# MicroController.net
KiCad netlist of a schematic drawn in Altium Designer
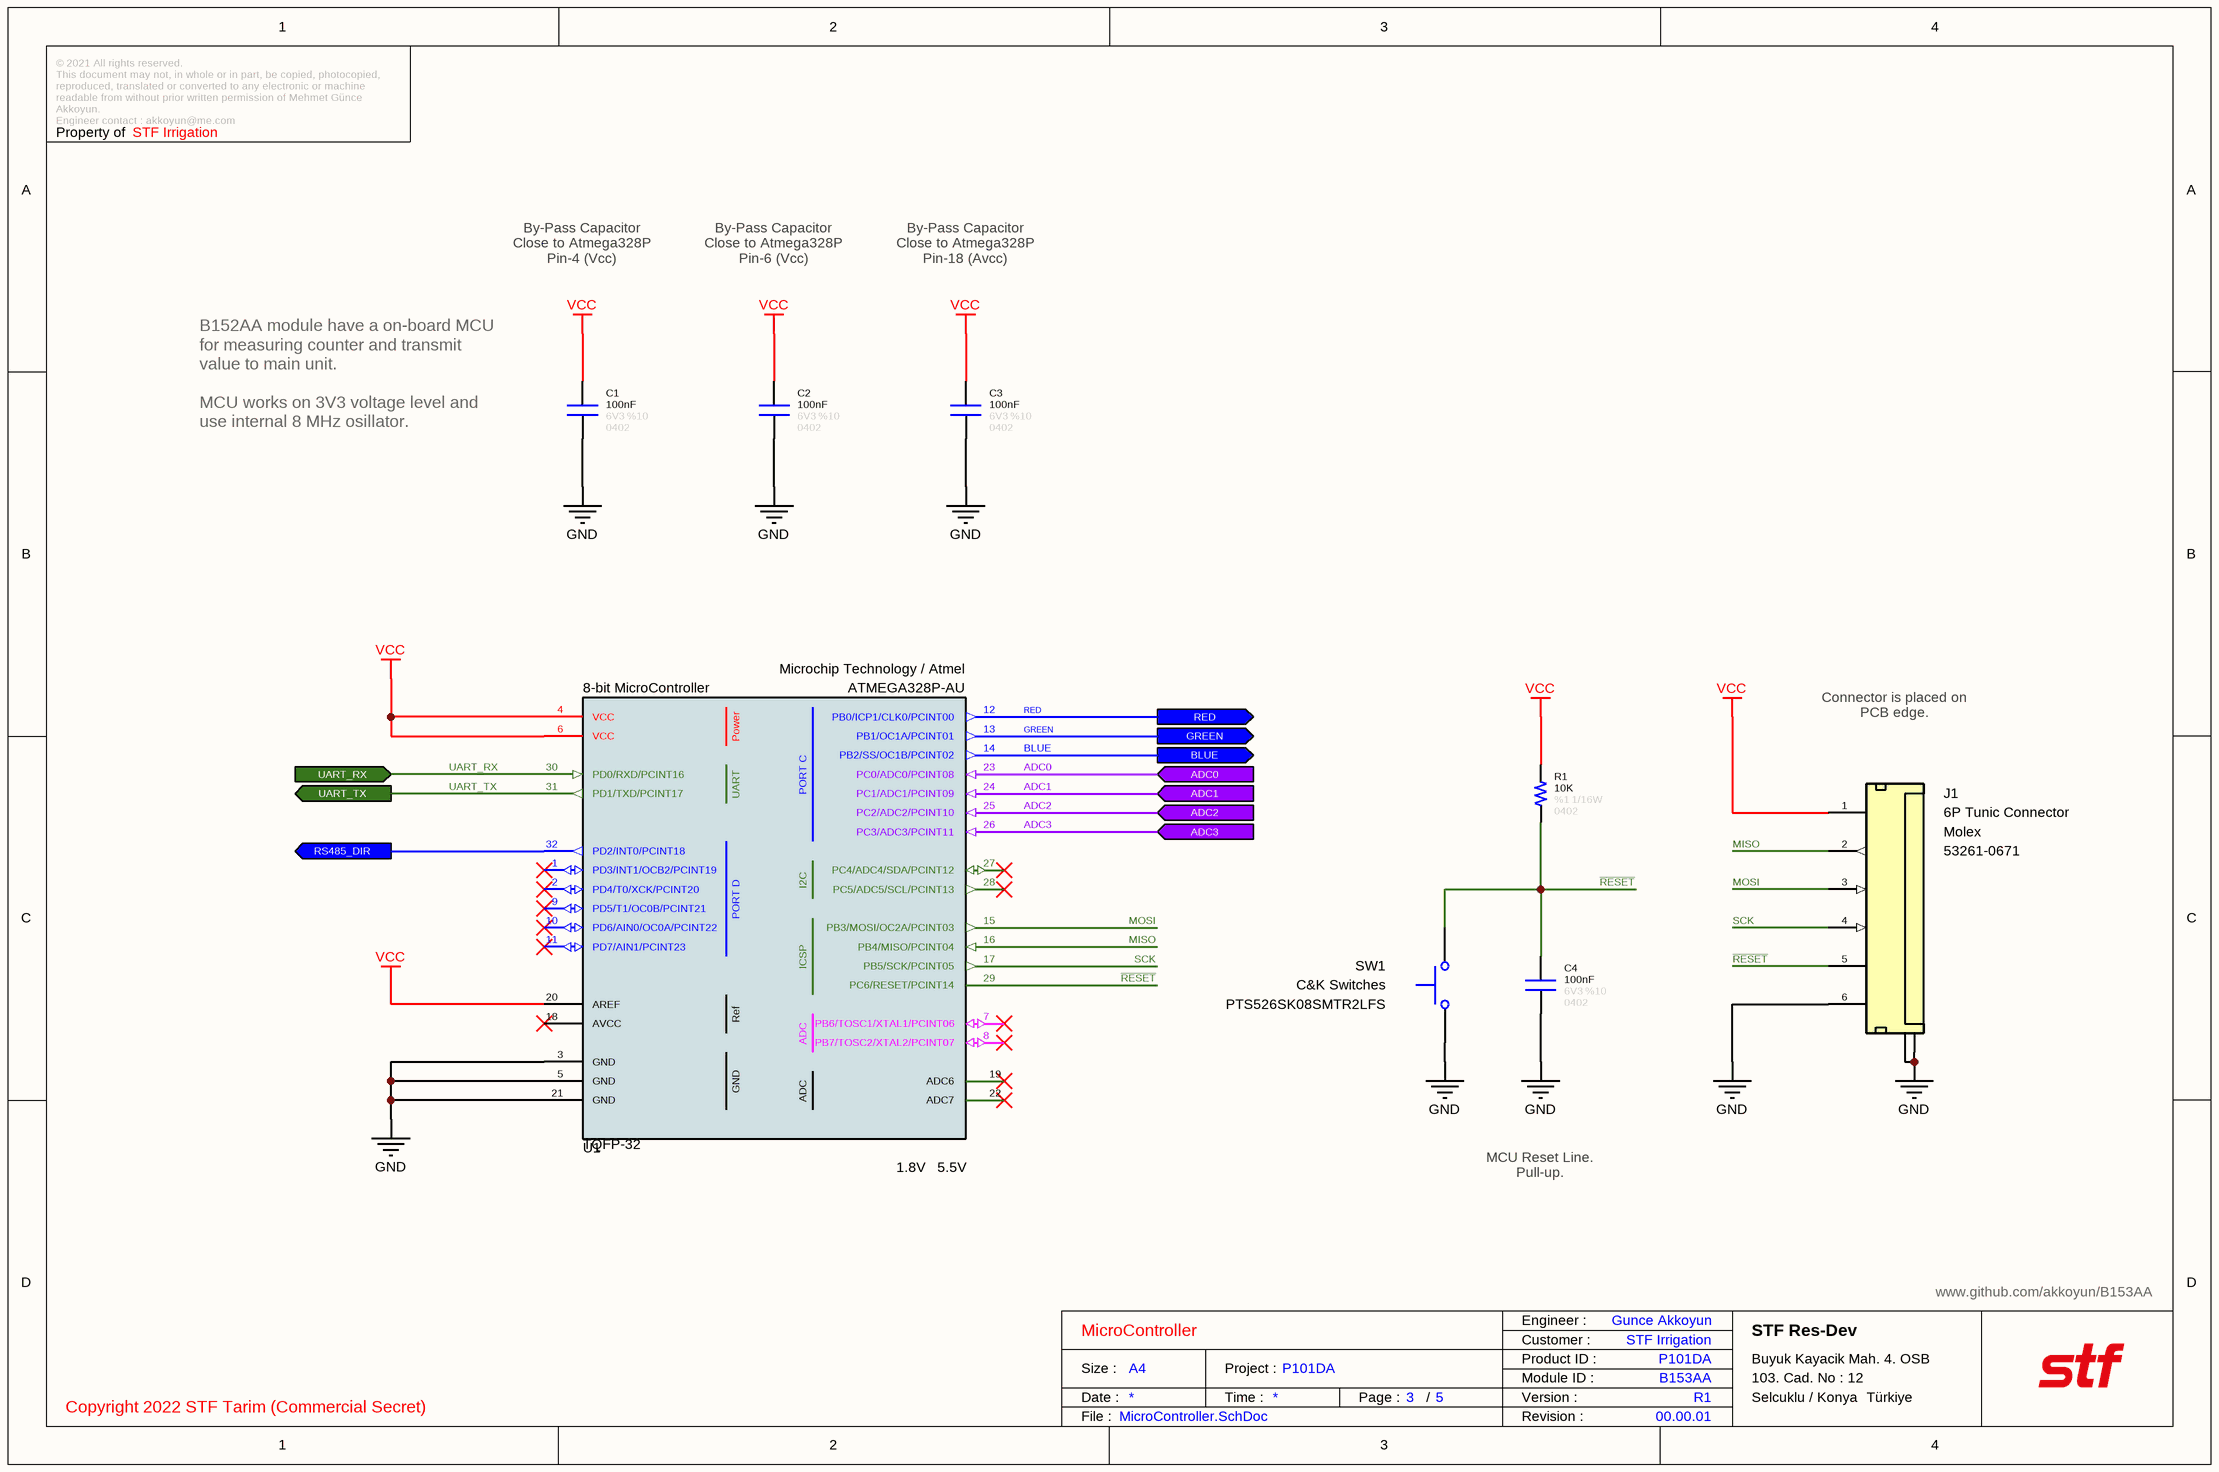
[diagram p0: MicroController.SchDoc]

(export (version "E")
  (design (tool "Eeschema 10.0.6"))
  (components
    (comp (ref "C1")
      (value "100nF")
      (footprint "CAPACITOR_0402")
      (description "Capacitor - 100nF [0402-6V3] (Ceramic)")
      (fields
        (field (name "MANUFACTURER PART NUMBER") "04026D104KAT4A")
        (field (name "TOLERANCE") "%10")
        (field (name "VOLTAGE") "6V3")
        (field (name "CASE") "0402")
        (field (name "Comment") "Capacitor - 100nF [0402] (Ceramic)")
      )
      (libsource (lib "P101DA_Library") (part "Capacitor - 100nF [0402-6V3]"))
    )
    (comp (ref "C2")
      (value "100nF")
      (footprint "CAPACITOR_0402")
      (description "Capacitor - 100nF [0402-6V3] (Ceramic)")
      (fields
        (field (name "MANUFACTURER PART NUMBER") "04026D104KAT4A")
        (field (name "TOLERANCE") "%10")
        (field (name "VOLTAGE") "6V3")
        (field (name "CASE") "0402")
        (field (name "Comment") "Capacitor - 100nF [0402] (Ceramic)")
      )
      (libsource (lib "P101DA_Library") (part "Capacitor - 100nF [0402-6V3]"))
    )
    (comp (ref "C3")
      (value "100nF")
      (footprint "CAPACITOR_0402")
      (description "Capacitor - 100nF [0402-6V3] (Ceramic)")
      (fields
        (field (name "MANUFACTURER PART NUMBER") "04026D104KAT4A")
        (field (name "TOLERANCE") "%10")
        (field (name "VOLTAGE") "6V3")
        (field (name "CASE") "0402")
        (field (name "Comment") "Capacitor - 100nF [0402] (Ceramic)")
      )
      (libsource (lib "P101DA_Library") (part "Capacitor - 100nF [0402-6V3]"))
    )
    (comp (ref "C4")
      (value "100nF")
      (footprint "CAPACITOR_0402")
      (description "Capacitor - 100nF [0402-6V3] (Ceramic)")
      (fields
        (field (name "MANUFACTURER PART NUMBER") "04026D104KAT4A")
        (field (name "TOLERANCE") "%10")
        (field (name "VOLTAGE") "6V3")
        (field (name "CASE") "0402")
        (field (name "Comment") "Capacitor - 100nF [0402] (Ceramic)")
      )
      (libsource (lib "P101DA_Library") (part "Capacitor - 100nF [0402-6V3]"))
    )
    (comp (ref "J1")
      (value "6P Tunic Connector")
      (footprint "Connector_Tunic 6P")
      (description "Mini Tunic Connector with 6P")
      (fields
        (field (name "MANUFACTURER PART NUMBER") "53261-0671")
        (field (name "MANUFACTURER NAME") "Molex")
      )
      (libsource (lib "P101DA_Library") (part "Connector - Mini Tunic 6P (1.25)"))
    )
    (comp (ref "R1")
      (value "10K")
      (footprint "RESISTOR_0402")
      (description "Thick Film Resistors - SMD 1/16 W 10 KOhm 1%")
      (fields
        (field (name "MANUFACTURER PART NUMBER") "CRCW040210K0FKED")
        (field (name "TOLERANCE") "%1")
        (field (name "CASE") "0402")
        (field (name "POWER") "1/16W")
        (field (name "Comment") "10K - 0402 - %1 - 1/16W")
      )
      (libsource (lib "P101DA_Library") (part "Resistor - 10K [0402]"))
    )
    (comp (ref "SW1")
      (value "PTS526SK08SMTR2LFS")
      (footprint "PTS526_Switch")
      (description "Switch Tactile N.O. SPST Flush Round Button Gull Wing 0.05A 12VDC 200000Cycles 2.45N SMD T/R")
      (fields
        (field (name "MANUFACTURER NAME") "C&K Switches")
        (field (name "MANUFACTURER PART NUMBER") "PTS526SK08SMTR2LFS")
      )
      (libsource (lib "P101DA_Library") (part "Switch - Push Button"))
    )
    (comp (ref "U1")
      (value "8-bit MicroController")
      (footprint "TQFN-32")
      (description "8-bit Microcontrollers - MCU 32KB In-system Flash 20MHz 1.8V-5.5V")
      (fields
        (field (name "SUPPLY VOLTAGE - MAX") "5.5V")
        (field (name "SUPPLY VOLTAGE - MIN") "1.8V")
        (field (name "MANUFACTURER NAME") "Microchip Technology / Atmel")
        (field (name "MANUFACTURER PART NUMBER") "ATMEGA328P-AU")
        (field (name "CASE") "TQFP-32")
      )
      (libsource (lib "P101DA_Library") (part "IC - ATMEGA328P-AU"))
    )
  )
  (nets
    (net (code "1") (name "/ADC0") (class "Default")
      (node (ref "U1") (pin "23") (pinfunction "PC0/ADC0/PCINT08_23") (pintype "input"))
    )
    (net (code "2") (name "/ADC1") (class "Default")
      (node (ref "U1") (pin "24") (pinfunction "PC1/ADC1/PCINT09_24") (pintype "input"))
    )
    (net (code "3") (name "/ADC2") (class "Default")
      (node (ref "U1") (pin "25") (pinfunction "PC2/ADC2/PCINT10_25") (pintype "input"))
    )
    (net (code "4") (name "/ADC3") (class "Default")
      (node (ref "U1") (pin "26") (pinfunction "PC3/ADC3/PCINT11_26") (pintype "input"))
    )
    (net (code "5") (name "/BLUE") (class "Default")
      (node (ref "U1") (pin "14") (pinfunction "PB2/SS/OC1B/PCINT02_14") (pintype "output"))
    )
    (net (code "6") (name "/GREEN") (class "Default")
      (node (ref "U1") (pin "13") (pinfunction "PB1/OC1A/PCINT01_13") (pintype "output"))
    )
    (net (code "7") (name "/MISO") (class "Default")
      (node (ref "J1") (pin "2") (pinfunction "M_DRV_2") (pintype "output"))
      (node (ref "U1") (pin "16") (pinfunction "PB4/MISO/PCINT04_16") (pintype "input"))
    )
    (net (code "8") (name "/MOSI") (class "Default")
      (node (ref "J1") (pin "3") (pinfunction "M_DRV_3") (pintype "input"))
      (node (ref "U1") (pin "15") (pinfunction "PB3/MOSI/OC2A/PCINT03_15") (pintype "output"))
    )
    (net (code "9") (name "/RED") (class "Default")
      (node (ref "U1") (pin "12") (pinfunction "PB0/ICP1/CLK0/PCINT00_12") (pintype "output"))
    )
    (net (code "10") (name "/RS485_DIR") (class "Default")
      (node (ref "U1") (pin "32") (pinfunction "PD2/INT0/PCINT18_32") (pintype "output"))
    )
    (net (code "11") (name "/SCK") (class "Default")
      (node (ref "J1") (pin "4") (pinfunction "M_DRV_4") (pintype "input"))
      (node (ref "U1") (pin "17") (pinfunction "PB5/SCK/PCINT05_17") (pintype "output"))
    )
    (net (code "12") (name "/UART_RX") (class "Default")
      (node (ref "U1") (pin "30") (pinfunction "PD0/RXD/PCINT16_30") (pintype "input"))
    )
    (net (code "13") (name "/UART_TX") (class "Default")
      (node (ref "U1") (pin "31") (pinfunction "PD1/TXD/PCINT17_31") (pintype "output"))
    )
    (net (code "14") (name "/~{RESET}") (class "Default")
      (node (ref "C4") (pin "2") (pinfunction "2_2") (pintype "passive"))
      (node (ref "J1") (pin "5") (pinfunction "M_DRV_5") (pintype "passive"))
      (node (ref "R1") (pin "1") (pinfunction "1_1") (pintype "passive"))
      (node (ref "SW1") (pin "2") (pinfunction "COM_2") (pintype "passive"))
      (node (ref "U1") (pin "29") (pinfunction "PC6/RESET/PCINT14_29") (pintype "passive"))
    )
    (net (code "15") (name "GND") (class "Default")
      (node (ref "C1") (pin "1") (pinfunction "1_1") (pintype "passive"))
      (node (ref "C2") (pin "1") (pinfunction "1_1") (pintype "passive"))
      (node (ref "C3") (pin "1") (pinfunction "1_1") (pintype "passive"))
      (node (ref "C4") (pin "1") (pinfunction "1_1") (pintype "passive"))
      (node (ref "J1") (pin "6") (pinfunction "M_DRV_6") (pintype "passive"))
      (node (ref "J1") (pin "7") (pinfunction "GND_7") (pintype "passive"))
      (node (ref "J1") (pin "8") (pinfunction "GND_8") (pintype "passive"))
      (node (ref "SW1") (pin "1") (pinfunction "NC_1") (pintype "passive"))
      (node (ref "U1") (pin "21") (pinfunction "GND_21") (pintype "power_in"))
      (node (ref "U1") (pin "3") (pinfunction "GND_3") (pintype "power_in"))
      (node (ref "U1") (pin "5") (pinfunction "GND_5") (pintype "power_in"))
    )
    (net (code "16") (name "VCC") (class "Default")
      (node (ref "C1") (pin "2") (pinfunction "2_2") (pintype "passive"))
      (node (ref "C2") (pin "2") (pinfunction "2_2") (pintype "passive"))
      (node (ref "C3") (pin "2") (pinfunction "2_2") (pintype "passive"))
      (node (ref "J1") (pin "1") (pinfunction "VBAT_1") (pintype "passive"))
      (node (ref "R1") (pin "2") (pinfunction "2_2") (pintype "passive"))
      (node (ref "U1") (pin "20") (pinfunction "AREF_20") (pintype "passive"))
      (node (ref "U1") (pin "4") (pinfunction "VCC_4") (pintype "power_in"))
      (node (ref "U1") (pin "6") (pinfunction "VCC_6") (pintype "power_in"))
    )
    (net (code "17") (name "unconnected-(U1-ADC6-Pad19)") (class "Default")
      (node (ref "U1") (pin "19") (pinfunction "ADC6_19") (pintype "passive+no_connect"))
    )
    (net (code "18") (name "unconnected-(U1-ADC7-Pad22)") (class "Default")
      (node (ref "U1") (pin "22") (pinfunction "ADC7_22") (pintype "passive+no_connect"))
    )
    (net (code "19") (name "unconnected-(U1-AVCC-Pad18)") (class "Default")
      (node (ref "U1") (pin "18") (pinfunction "AVCC_18") (pintype "passive+no_connect"))
    )
    (net (code "20") (name "unconnected-(U1-PB6{slash}TOSC1{slash}XTAL1{slash}PCINT06-Pad7)") (class "Default")
      (node (ref "U1") (pin "7") (pinfunction "PB6/TOSC1/XTAL1/PCINT06_7") (pintype "bidirectional+no_connect"))
    )
    (net (code "21") (name "unconnected-(U1-PB7{slash}TOSC2{slash}XTAL2{slash}PCINT07-Pad8)") (class "Default")
      (node (ref "U1") (pin "8") (pinfunction "PB7/TOSC2/XTAL2/PCINT07_8") (pintype "bidirectional+no_connect"))
    )
    (net (code "22") (name "unconnected-(U1-PC4{slash}ADC4{slash}SDA{slash}PCINT12-Pad27)") (class "Default")
      (node (ref "U1") (pin "27") (pinfunction "PC4/ADC4/SDA/PCINT12_27") (pintype "bidirectional+no_connect"))
    )
    (net (code "23") (name "unconnected-(U1-PC5{slash}ADC5{slash}SCL{slash}PCINT13-Pad28)") (class "Default")
      (node (ref "U1") (pin "28") (pinfunction "PC5/ADC5/SCL/PCINT13_28") (pintype "output+no_connect"))
    )
    (net (code "24") (name "unconnected-(U1-PD3{slash}INT1{slash}OCB2{slash}PCINT19-Pad1)") (class "Default")
      (node (ref "U1") (pin "1") (pinfunction "PD3/INT1/OCB2/PCINT19_1") (pintype "bidirectional+no_connect"))
    )
    (net (code "25") (name "unconnected-(U1-PD4{slash}T0{slash}XCK{slash}PCINT20-Pad2)") (class "Default")
      (node (ref "U1") (pin "2") (pinfunction "PD4/T0/XCK/PCINT20_2") (pintype "bidirectional+no_connect"))
    )
    (net (code "26") (name "unconnected-(U1-PD5{slash}T1{slash}OC0B{slash}PCINT21-Pad9)") (class "Default")
      (node (ref "U1") (pin "9") (pinfunction "PD5/T1/OC0B/PCINT21_9") (pintype "bidirectional+no_connect"))
    )
    (net (code "27") (name "unconnected-(U1-PD6{slash}AIN0{slash}OC0A{slash}PCINT22-Pad10)") (class "Default")
      (node (ref "U1") (pin "10") (pinfunction "PD6/AIN0/OC0A/PCINT22_10") (pintype "bidirectional+no_connect"))
    )
    (net (code "28") (name "unconnected-(U1-PD7{slash}AIN1{slash}PCINT23-Pad11)") (class "Default")
      (node (ref "U1") (pin "11") (pinfunction "PD7/AIN1/PCINT23_11") (pintype "bidirectional+no_connect"))
    )
  )
)
